# BTB_CONNECTOR.net
KiCad netlist of a schematic drawn in Altium Designer
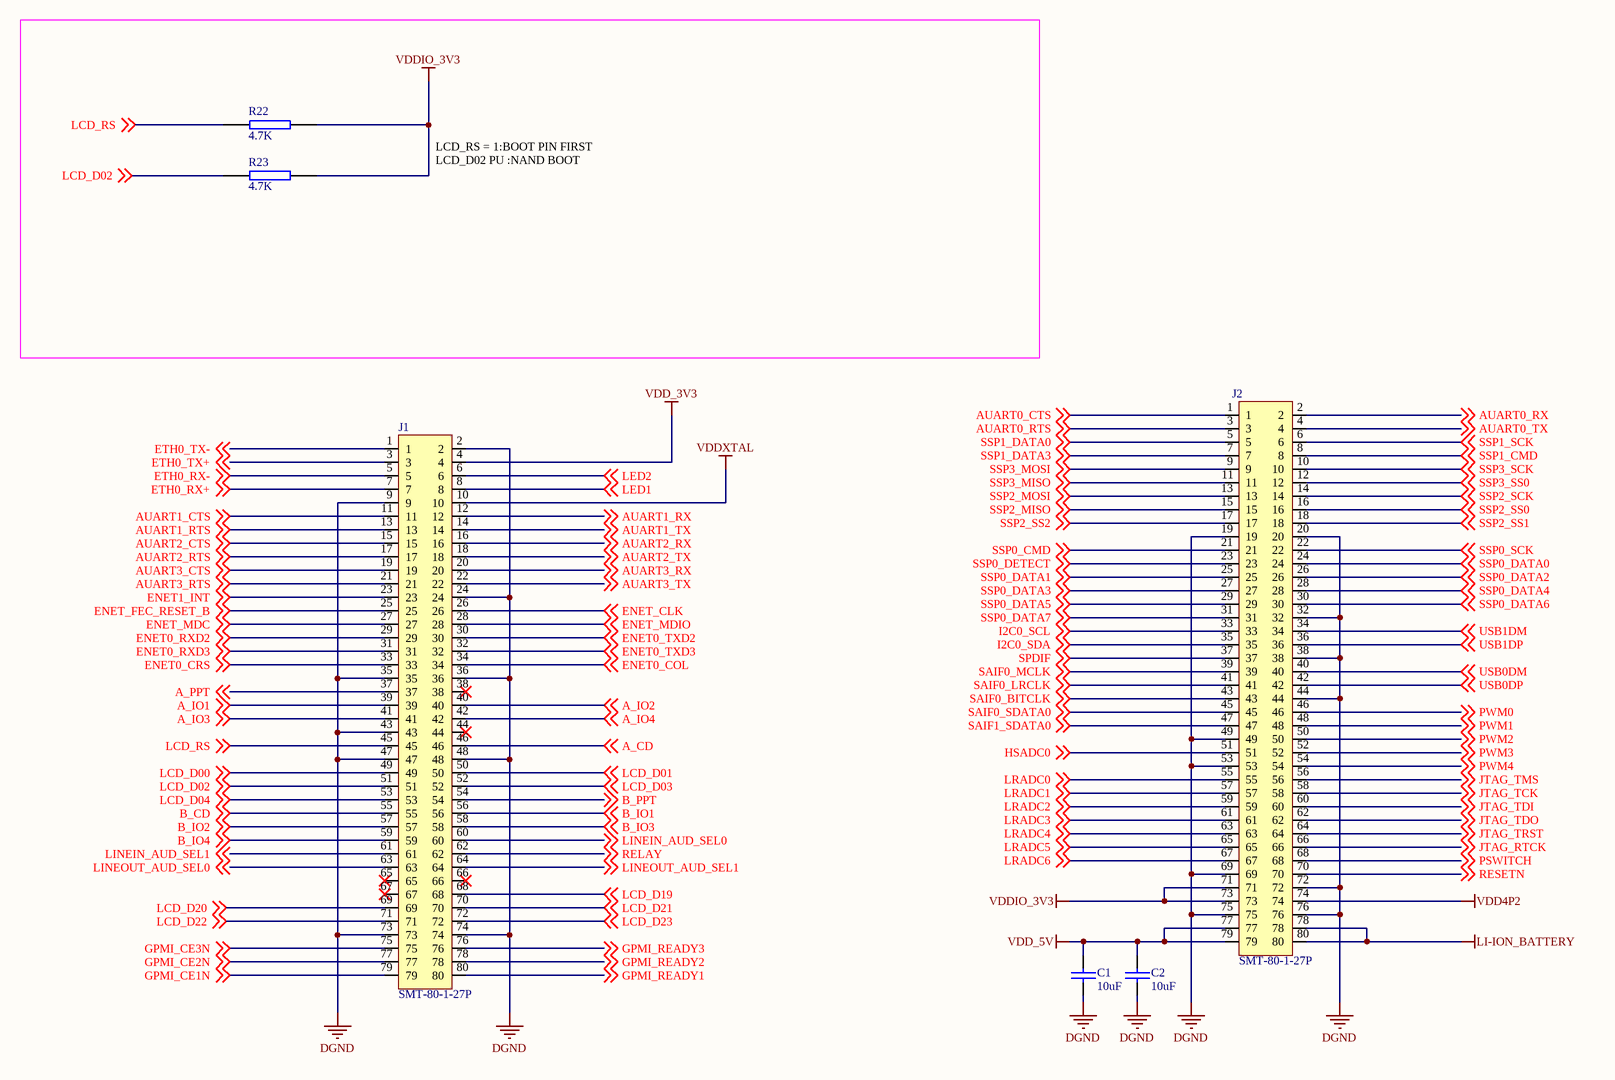
[diagram p0: BTB CONNECTOR.SchDoc]

(export (version "E")
  (design (tool "Eeschema 10.0.6"))
  (components
    (comp (ref "C1")
      (value "10uF")
      (footprint "C0805")
      (description "Capacitor")
      (libsource (lib "AirGateway") (part "CAP"))
    )
    (comp (ref "C2")
      (value "10uF")
      (footprint "C0805")
      (description "Capacitor")
      (libsource (lib "AirGateway") (part "CAP"))
    )
    (comp (ref "J1")
      (value "SMT-80-1-27P")
      (footprint "DB40X2-1.27")
      (libsource (lib "Schlib1") (part "SMT-80-1-27P"))
    )
    (comp (ref "J2")
      (value "SMT-80-1-27P")
      (footprint "DB40X2-1.27")
      (libsource (lib "Schlib1") (part "SMT-80-1-27P"))
    )
    (comp (ref "R22") (value "4.7K") (footprint "C0402") (libsource (lib "AirGateway") (part "RES2")))
    (comp (ref "R23") (value "4.7K") (footprint "C0402") (libsource (lib "AirGateway") (part "RES2")))
  )
  (nets
    (net (code "1") (name "AUART0_CTS") (class "Default")
      (node (ref "J2") (pin "1") (pinfunction "1_1") (pintype "passive"))
    )
    (net (code "2") (name "AUART0_RTS") (class "Default")
      (node (ref "J2") (pin "3") (pinfunction "3_3") (pintype "passive"))
    )
    (net (code "3") (name "AUART0_RX") (class "Default")
      (node (ref "J2") (pin "2") (pinfunction "2_2") (pintype "passive"))
    )
    (net (code "4") (name "AUART0_TX") (class "Default")
      (node (ref "J2") (pin "4") (pinfunction "4_4") (pintype "passive"))
    )
    (net (code "5") (name "AUART1_CTS") (class "Default")
      (node (ref "J1") (pin "11") (pinfunction "11_11") (pintype "passive"))
    )
    (net (code "6") (name "AUART1_RTS") (class "Default")
      (node (ref "J1") (pin "13") (pinfunction "13_13") (pintype "passive"))
    )
    (net (code "7") (name "AUART1_RX") (class "Default")
      (node (ref "J1") (pin "12") (pinfunction "12_12") (pintype "passive"))
    )
    (net (code "8") (name "AUART1_TX") (class "Default")
      (node (ref "J1") (pin "14") (pinfunction "14_14") (pintype "passive"))
    )
    (net (code "9") (name "AUART2_CTS") (class "Default")
      (node (ref "J1") (pin "15") (pinfunction "15_15") (pintype "passive"))
    )
    (net (code "10") (name "AUART2_RTS") (class "Default")
      (node (ref "J1") (pin "17") (pinfunction "17_17") (pintype "passive"))
    )
    (net (code "11") (name "AUART2_RX") (class "Default")
      (node (ref "J1") (pin "16") (pinfunction "16_16") (pintype "passive"))
    )
    (net (code "12") (name "AUART2_TX") (class "Default")
      (node (ref "J1") (pin "18") (pinfunction "18_18") (pintype "passive"))
    )
    (net (code "13") (name "AUART3_CTS") (class "Default")
      (node (ref "J1") (pin "19") (pinfunction "19_19") (pintype "passive"))
    )
    (net (code "14") (name "AUART3_RTS") (class "Default")
      (node (ref "J1") (pin "21") (pinfunction "21_21") (pintype "passive"))
    )
    (net (code "15") (name "AUART3_RX") (class "Default")
      (node (ref "J1") (pin "20") (pinfunction "20_20") (pintype "passive"))
    )
    (net (code "16") (name "AUART3_TX") (class "Default")
      (node (ref "J1") (pin "22") (pinfunction "22_22") (pintype "passive"))
    )
    (net (code "17") (name "A_CD") (class "Default")
      (node (ref "J1") (pin "46") (pinfunction "46_46") (pintype "passive"))
    )
    (net (code "18") (name "A_IO1") (class "Default")
      (node (ref "J1") (pin "39") (pinfunction "39_39") (pintype "passive"))
    )
    (net (code "19") (name "A_IO2") (class "Default")
      (node (ref "J1") (pin "40") (pinfunction "40_40") (pintype "passive"))
    )
    (net (code "20") (name "A_IO3") (class "Default")
      (node (ref "J1") (pin "41") (pinfunction "41_41") (pintype "passive"))
    )
    (net (code "21") (name "A_IO4") (class "Default")
      (node (ref "J1") (pin "42") (pinfunction "42_42") (pintype "passive"))
    )
    (net (code "22") (name "A_PPT") (class "Default")
      (node (ref "J1") (pin "37") (pinfunction "37_37") (pintype "passive"))
    )
    (net (code "23") (name "B_CD") (class "Default")
      (node (ref "J1") (pin "55") (pinfunction "55_55") (pintype "passive"))
    )
    (net (code "24") (name "B_IO1") (class "Default")
      (node (ref "J1") (pin "56") (pinfunction "56_56") (pintype "passive"))
    )
    (net (code "25") (name "B_IO2") (class "Default")
      (node (ref "J1") (pin "57") (pinfunction "57_57") (pintype "passive"))
    )
    (net (code "26") (name "B_IO3") (class "Default")
      (node (ref "J1") (pin "58") (pinfunction "58_58") (pintype "passive"))
    )
    (net (code "27") (name "B_IO4") (class "Default")
      (node (ref "J1") (pin "59") (pinfunction "59_59") (pintype "passive"))
    )
    (net (code "28") (name "B_PPT") (class "Default")
      (node (ref "J1") (pin "54") (pinfunction "54_54") (pintype "passive"))
    )
    (net (code "29") (name "DGND") (class "Default")
      (node (ref "C1") (pin "2") (pinfunction "2_2") (pintype "passive"))
      (node (ref "C2") (pin "2") (pinfunction "2_2") (pintype "passive"))
      (node (ref "J1") (pin "2") (pinfunction "2_2") (pintype "passive"))
      (node (ref "J1") (pin "24") (pinfunction "24_24") (pintype "passive"))
      (node (ref "J1") (pin "35") (pinfunction "35_35") (pintype "passive"))
      (node (ref "J1") (pin "36") (pinfunction "36_36") (pintype "passive"))
      (node (ref "J1") (pin "43") (pinfunction "43_43") (pintype "passive"))
      (node (ref "J1") (pin "47") (pinfunction "47_47") (pintype "passive"))
      (node (ref "J1") (pin "48") (pinfunction "48_48") (pintype "passive"))
      (node (ref "J1") (pin "73") (pinfunction "73_73") (pintype "passive"))
      (node (ref "J1") (pin "74") (pinfunction "74_74") (pintype "passive"))
      (node (ref "J1") (pin "9") (pinfunction "9_9") (pintype "passive"))
      (node (ref "J2") (pin "19") (pinfunction "19_19") (pintype "passive"))
      (node (ref "J2") (pin "20") (pinfunction "20_20") (pintype "passive"))
      (node (ref "J2") (pin "32") (pinfunction "32_32") (pintype "passive"))
      (node (ref "J2") (pin "38") (pinfunction "38_38") (pintype "passive"))
      (node (ref "J2") (pin "44") (pinfunction "44_44") (pintype "passive"))
      (node (ref "J2") (pin "49") (pinfunction "49_49") (pintype "passive"))
      (node (ref "J2") (pin "53") (pinfunction "53_53") (pintype "passive"))
      (node (ref "J2") (pin "69") (pinfunction "69_69") (pintype "passive"))
      (node (ref "J2") (pin "72") (pinfunction "72_72") (pintype "passive"))
      (node (ref "J2") (pin "75") (pinfunction "75_75") (pintype "passive"))
      (node (ref "J2") (pin "76") (pinfunction "76_76") (pintype "passive"))
    )
    (net (code "30") (name "ENET0_COL") (class "Default")
      (node (ref "J1") (pin "34") (pinfunction "34_34") (pintype "passive"))
    )
    (net (code "31") (name "ENET0_CRS") (class "Default")
      (node (ref "J1") (pin "33") (pinfunction "33_33") (pintype "passive"))
    )
    (net (code "32") (name "ENET0_RXD2") (class "Default")
      (node (ref "J1") (pin "29") (pinfunction "29_29") (pintype "passive"))
    )
    (net (code "33") (name "ENET0_RXD3") (class "Default")
      (node (ref "J1") (pin "31") (pinfunction "31_31") (pintype "passive"))
    )
    (net (code "34") (name "ENET0_TXD2") (class "Default")
      (node (ref "J1") (pin "30") (pinfunction "30_30") (pintype "passive"))
    )
    (net (code "35") (name "ENET0_TXD3") (class "Default")
      (node (ref "J1") (pin "32") (pinfunction "32_32") (pintype "passive"))
    )
    (net (code "36") (name "ENET1_INT") (class "Default")
      (node (ref "J1") (pin "23") (pinfunction "23_23") (pintype "passive"))
    )
    (net (code "37") (name "ENET_CLK") (class "Default")
      (node (ref "J1") (pin "26") (pinfunction "26_26") (pintype "passive"))
    )
    (net (code "38") (name "ENET_FEC_RESET_B") (class "Default")
      (node (ref "J1") (pin "25") (pinfunction "25_25") (pintype "passive"))
    )
    (net (code "39") (name "ENET_MDC") (class "Default")
      (node (ref "J1") (pin "27") (pinfunction "27_27") (pintype "passive"))
    )
    (net (code "40") (name "ENET_MDIO") (class "Default")
      (node (ref "J1") (pin "28") (pinfunction "28_28") (pintype "passive"))
    )
    (net (code "41") (name "ETH0_RX+") (class "Default")
      (node (ref "J1") (pin "7") (pinfunction "7_7") (pintype "passive"))
    )
    (net (code "42") (name "ETH0_RX-") (class "Default")
      (node (ref "J1") (pin "5") (pinfunction "5_5") (pintype "passive"))
    )
    (net (code "43") (name "ETH0_TX+") (class "Default")
      (node (ref "J1") (pin "3") (pinfunction "3_3") (pintype "passive"))
    )
    (net (code "44") (name "ETH0_TX-") (class "Default")
      (node (ref "J1") (pin "1") (pinfunction "1_1") (pintype "passive"))
    )
    (net (code "45") (name "GPMI_CE1N") (class "Default")
      (node (ref "J1") (pin "79") (pinfunction "79_79") (pintype "passive"))
    )
    (net (code "46") (name "GPMI_CE2N") (class "Default")
      (node (ref "J1") (pin "77") (pinfunction "77_77") (pintype "passive"))
    )
    (net (code "47") (name "GPMI_CE3N") (class "Default")
      (node (ref "J1") (pin "75") (pinfunction "75_75") (pintype "passive"))
    )
    (net (code "48") (name "GPMI_READY1") (class "Default")
      (node (ref "J1") (pin "80") (pinfunction "80_80") (pintype "passive"))
    )
    (net (code "49") (name "GPMI_READY2") (class "Default")
      (node (ref "J1") (pin "78") (pinfunction "78_78") (pintype "passive"))
    )
    (net (code "50") (name "GPMI_READY3") (class "Default")
      (node (ref "J1") (pin "76") (pinfunction "76_76") (pintype "passive"))
    )
    (net (code "51") (name "HSADC0") (class "Default")
      (node (ref "J2") (pin "51") (pinfunction "51_51") (pintype "passive"))
    )
    (net (code "52") (name "I2C0_SCL") (class "Default")
      (node (ref "J2") (pin "33") (pinfunction "33_33") (pintype "passive"))
    )
    (net (code "53") (name "I2C0_SDA") (class "Default")
      (node (ref "J2") (pin "35") (pinfunction "35_35") (pintype "passive"))
    )
    (net (code "54") (name "JTAG_RTCK") (class "Default")
      (node (ref "J2") (pin "66") (pinfunction "66_66") (pintype "passive"))
    )
    (net (code "55") (name "JTAG_TCK") (class "Default")
      (node (ref "J2") (pin "58") (pinfunction "58_58") (pintype "passive"))
    )
    (net (code "56") (name "JTAG_TDI") (class "Default")
      (node (ref "J2") (pin "60") (pinfunction "60_60") (pintype "passive"))
    )
    (net (code "57") (name "JTAG_TDO") (class "Default")
      (node (ref "J2") (pin "62") (pinfunction "62_62") (pintype "passive"))
    )
    (net (code "58") (name "JTAG_TMS") (class "Default")
      (node (ref "J2") (pin "56") (pinfunction "56_56") (pintype "passive"))
    )
    (net (code "59") (name "JTAG_TRST") (class "Default")
      (node (ref "J2") (pin "64") (pinfunction "64_64") (pintype "passive"))
    )
    (net (code "60") (name "LCD_D00") (class "Default")
      (node (ref "J1") (pin "49") (pinfunction "49_49") (pintype "passive"))
    )
    (net (code "61") (name "LCD_D01") (class "Default")
      (node (ref "J1") (pin "50") (pinfunction "50_50") (pintype "passive"))
    )
    (net (code "62") (name "LCD_D02") (class "Default")
      (node (ref "J1") (pin "51") (pinfunction "51_51") (pintype "passive"))
      (node (ref "R23") (pin "2") (pinfunction "2_2") (pintype "passive"))
    )
    (net (code "63") (name "LCD_D03") (class "Default")
      (node (ref "J1") (pin "52") (pinfunction "52_52") (pintype "passive"))
    )
    (net (code "64") (name "LCD_D04") (class "Default")
      (node (ref "J1") (pin "53") (pinfunction "53_53") (pintype "passive"))
    )
    (net (code "65") (name "LCD_D19") (class "Default")
      (node (ref "J1") (pin "68") (pinfunction "68_68") (pintype "passive"))
    )
    (net (code "66") (name "LCD_D20") (class "Default")
      (node (ref "J1") (pin "69") (pinfunction "69_69") (pintype "passive"))
    )
    (net (code "67") (name "LCD_D21") (class "Default")
      (node (ref "J1") (pin "70") (pinfunction "70_70") (pintype "passive"))
    )
    (net (code "68") (name "LCD_D22") (class "Default")
      (node (ref "J1") (pin "71") (pinfunction "71_71") (pintype "passive"))
    )
    (net (code "69") (name "LCD_D23") (class "Default")
      (node (ref "J1") (pin "72") (pinfunction "72_72") (pintype "passive"))
    )
    (net (code "70") (name "LCD_RS") (class "Default")
      (node (ref "J1") (pin "45") (pinfunction "45_45") (pintype "passive"))
      (node (ref "R22") (pin "2") (pinfunction "2_2") (pintype "passive"))
    )
    (net (code "71") (name "LED1") (class "Default")
      (node (ref "J1") (pin "8") (pinfunction "8_8") (pintype "passive"))
    )
    (net (code "72") (name "LED2") (class "Default")
      (node (ref "J1") (pin "6") (pinfunction "6_6") (pintype "passive"))
    )
    (net (code "73") (name "LI-ION_BATTERY") (class "Default")
      (node (ref "J2") (pin "78") (pinfunction "78_78") (pintype "passive"))
      (node (ref "J2") (pin "80") (pinfunction "80_80") (pintype "passive"))
    )
    (net (code "74") (name "LINEIN_AUD_SEL0") (class "Default")
      (node (ref "J1") (pin "60") (pinfunction "60_60") (pintype "passive"))
    )
    (net (code "75") (name "LINEIN_AUD_SEL1") (class "Default")
      (node (ref "J1") (pin "61") (pinfunction "61_61") (pintype "passive"))
    )
    (net (code "76") (name "LINEOUT_AUD_SEL0") (class "Default")
      (node (ref "J1") (pin "63") (pinfunction "63_63") (pintype "passive"))
    )
    (net (code "77") (name "LINEOUT_AUD_SEL1") (class "Default")
      (node (ref "J1") (pin "64") (pinfunction "64_64") (pintype "passive"))
    )
    (net (code "78") (name "LRADC0") (class "Default")
      (node (ref "J2") (pin "55") (pinfunction "55_55") (pintype "passive"))
    )
    (net (code "79") (name "LRADC1") (class "Default")
      (node (ref "J2") (pin "57") (pinfunction "57_57") (pintype "passive"))
    )
    (net (code "80") (name "LRADC2") (class "Default")
      (node (ref "J2") (pin "59") (pinfunction "59_59") (pintype "passive"))
    )
    (net (code "81") (name "LRADC3") (class "Default")
      (node (ref "J2") (pin "61") (pinfunction "61_61") (pintype "passive"))
    )
    (net (code "82") (name "LRADC4") (class "Default")
      (node (ref "J2") (pin "63") (pinfunction "63_63") (pintype "passive"))
    )
    (net (code "83") (name "LRADC5") (class "Default")
      (node (ref "J2") (pin "65") (pinfunction "65_65") (pintype "passive"))
    )
    (net (code "84") (name "LRADC6") (class "Default")
      (node (ref "J2") (pin "67") (pinfunction "67_67") (pintype "passive"))
    )
    (net (code "85") (name "PSWITCH") (class "Default")
      (node (ref "J2") (pin "68") (pinfunction "68_68") (pintype "passive"))
    )
    (net (code "86") (name "PWM0") (class "Default")
      (node (ref "J2") (pin "46") (pinfunction "46_46") (pintype "passive"))
    )
    (net (code "87") (name "PWM1") (class "Default")
      (node (ref "J2") (pin "48") (pinfunction "48_48") (pintype "passive"))
    )
    (net (code "88") (name "PWM2") (class "Default")
      (node (ref "J2") (pin "50") (pinfunction "50_50") (pintype "passive"))
    )
    (net (code "89") (name "PWM3") (class "Default")
      (node (ref "J2") (pin "52") (pinfunction "52_52") (pintype "passive"))
    )
    (net (code "90") (name "PWM4") (class "Default")
      (node (ref "J2") (pin "54") (pinfunction "54_54") (pintype "passive"))
    )
    (net (code "91") (name "RELAY") (class "Default")
      (node (ref "J1") (pin "62") (pinfunction "62_62") (pintype "passive"))
    )
    (net (code "92") (name "RESETN") (class "Default")
      (node (ref "J2") (pin "70") (pinfunction "70_70") (pintype "passive"))
    )
    (net (code "93") (name "SAIF0_BITCLK") (class "Default")
      (node (ref "J2") (pin "43") (pinfunction "43_43") (pintype "passive"))
    )
    (net (code "94") (name "SAIF0_LRCLK") (class "Default")
      (node (ref "J2") (pin "41") (pinfunction "41_41") (pintype "passive"))
    )
    (net (code "95") (name "SAIF0_MCLK") (class "Default")
      (node (ref "J2") (pin "39") (pinfunction "39_39") (pintype "passive"))
    )
    (net (code "96") (name "SAIF0_SDATA0") (class "Default")
      (node (ref "J2") (pin "45") (pinfunction "45_45") (pintype "passive"))
    )
    (net (code "97") (name "SAIF1_SDATA0") (class "Default")
      (node (ref "J2") (pin "47") (pinfunction "47_47") (pintype "passive"))
    )
    (net (code "98") (name "SPDIF") (class "Default")
      (node (ref "J2") (pin "37") (pinfunction "37_37") (pintype "passive"))
    )
    (net (code "99") (name "SSP0_CMD") (class "Default")
      (node (ref "J2") (pin "21") (pinfunction "21_21") (pintype "passive"))
    )
    (net (code "100") (name "SSP0_DATA0") (class "Default")
      (node (ref "J2") (pin "24") (pinfunction "24_24") (pintype "passive"))
    )
    (net (code "101") (name "SSP0_DATA1") (class "Default")
      (node (ref "J2") (pin "25") (pinfunction "25_25") (pintype "passive"))
    )
    (net (code "102") (name "SSP0_DATA2") (class "Default")
      (node (ref "J2") (pin "26") (pinfunction "26_26") (pintype "passive"))
    )
    (net (code "103") (name "SSP0_DATA3") (class "Default")
      (node (ref "J2") (pin "27") (pinfunction "27_27") (pintype "passive"))
    )
    (net (code "104") (name "SSP0_DATA4") (class "Default")
      (node (ref "J2") (pin "28") (pinfunction "28_28") (pintype "passive"))
    )
    (net (code "105") (name "SSP0_DATA5") (class "Default")
      (node (ref "J2") (pin "29") (pinfunction "29_29") (pintype "passive"))
    )
    (net (code "106") (name "SSP0_DATA6") (class "Default")
      (node (ref "J2") (pin "30") (pinfunction "30_30") (pintype "passive"))
    )
    (net (code "107") (name "SSP0_DATA7") (class "Default")
      (node (ref "J2") (pin "31") (pinfunction "31_31") (pintype "passive"))
    )
    (net (code "108") (name "SSP0_DETECT") (class "Default")
      (node (ref "J2") (pin "23") (pinfunction "23_23") (pintype "passive"))
    )
    (net (code "109") (name "SSP0_SCK") (class "Default")
      (node (ref "J2") (pin "22") (pinfunction "22_22") (pintype "passive"))
    )
    (net (code "110") (name "SSP1_CMD") (class "Default")
      (node (ref "J2") (pin "8") (pinfunction "8_8") (pintype "passive"))
    )
    (net (code "111") (name "SSP1_DATA0") (class "Default")
      (node (ref "J2") (pin "5") (pinfunction "5_5") (pintype "passive"))
    )
    (net (code "112") (name "SSP1_DATA3") (class "Default")
      (node (ref "J2") (pin "7") (pinfunction "7_7") (pintype "passive"))
    )
    (net (code "113") (name "SSP1_SCK") (class "Default")
      (node (ref "J2") (pin "6") (pinfunction "6_6") (pintype "passive"))
    )
    (net (code "114") (name "SSP2_MISO") (class "Default")
      (node (ref "J2") (pin "15") (pinfunction "15_15") (pintype "passive"))
    )
    (net (code "115") (name "SSP2_MOSI") (class "Default")
      (node (ref "J2") (pin "13") (pinfunction "13_13") (pintype "passive"))
    )
    (net (code "116") (name "SSP2_SCK") (class "Default")
      (node (ref "J2") (pin "14") (pinfunction "14_14") (pintype "passive"))
    )
    (net (code "117") (name "SSP2_SS0") (class "Default")
      (node (ref "J2") (pin "16") (pinfunction "16_16") (pintype "passive"))
    )
    (net (code "118") (name "SSP2_SS1") (class "Default")
      (node (ref "J2") (pin "18") (pinfunction "18_18") (pintype "passive"))
    )
    (net (code "119") (name "SSP2_SS2") (class "Default")
      (node (ref "J2") (pin "17") (pinfunction "17_17") (pintype "passive"))
    )
    (net (code "120") (name "SSP3_MISO") (class "Default")
      (node (ref "J2") (pin "11") (pinfunction "11_11") (pintype "passive"))
    )
    (net (code "121") (name "SSP3_MOSI") (class "Default")
      (node (ref "J2") (pin "9") (pinfunction "9_9") (pintype "passive"))
    )
    (net (code "122") (name "SSP3_SCK") (class "Default")
      (node (ref "J2") (pin "10") (pinfunction "10_10") (pintype "passive"))
    )
    (net (code "123") (name "SSP3_SS0") (class "Default")
      (node (ref "J2") (pin "12") (pinfunction "12_12") (pintype "passive"))
    )
    (net (code "124") (name "USB0DM") (class "Default")
      (node (ref "J2") (pin "40") (pinfunction "40_40") (pintype "passive"))
    )
    (net (code "125") (name "USB0DP") (class "Default")
      (node (ref "J2") (pin "42") (pinfunction "42_42") (pintype "passive"))
    )
    (net (code "126") (name "USB1DM") (class "Default")
      (node (ref "J2") (pin "34") (pinfunction "34_34") (pintype "passive"))
    )
    (net (code "127") (name "USB1DP") (class "Default")
      (node (ref "J2") (pin "36") (pinfunction "36_36") (pintype "passive"))
    )
    (net (code "128") (name "VDD4P2") (class "Default")
      (node (ref "J2") (pin "74") (pinfunction "74_74") (pintype "passive"))
    )
    (net (code "129") (name "VDDIO_3V3") (class "Default")
      (node (ref "J2") (pin "71") (pinfunction "71_71") (pintype "passive"))
      (node (ref "J2") (pin "73") (pinfunction "73_73") (pintype "passive"))
      (node (ref "R22") (pin "1") (pinfunction "1_1") (pintype "passive"))
      (node (ref "R23") (pin "1") (pinfunction "1_1") (pintype "passive"))
    )
    (net (code "130") (name "VDDXTAL") (class "Default")
      (node (ref "J1") (pin "10") (pinfunction "10_10") (pintype "passive"))
    )
    (net (code "131") (name "VDD_3V3") (class "Default")
      (node (ref "J1") (pin "4") (pinfunction "4_4") (pintype "passive"))
    )
    (net (code "132") (name "VDD_5V") (class "Default")
      (node (ref "C1") (pin "1") (pinfunction "1_1") (pintype "passive"))
      (node (ref "C2") (pin "1") (pinfunction "1_1") (pintype "passive"))
      (node (ref "J2") (pin "77") (pinfunction "77_77") (pintype "passive"))
      (node (ref "J2") (pin "79") (pinfunction "79_79") (pintype "passive"))
    )
    (net (code "133") (name "unconnected-(J1-Pad38)") (class "Default")
      (node (ref "J1") (pin "38") (pinfunction "38_38") (pintype "passive+no_connect"))
    )
    (net (code "134") (name "unconnected-(J1-Pad44)") (class "Default")
      (node (ref "J1") (pin "44") (pinfunction "44_44") (pintype "passive+no_connect"))
    )
    (net (code "135") (name "unconnected-(J1-Pad65)") (class "Default")
      (node (ref "J1") (pin "65") (pinfunction "65_65") (pintype "passive+no_connect"))
    )
    (net (code "136") (name "unconnected-(J1-Pad66)") (class "Default")
      (node (ref "J1") (pin "66") (pinfunction "66_66") (pintype "passive+no_connect"))
    )
    (net (code "137") (name "unconnected-(J1-Pad67)") (class "Default")
      (node (ref "J1") (pin "67") (pinfunction "67_67") (pintype "passive+no_connect"))
    )
  )
)
